# SD_w_hexconverter.net
KiCad netlist of a schematic drawn in EAGLE
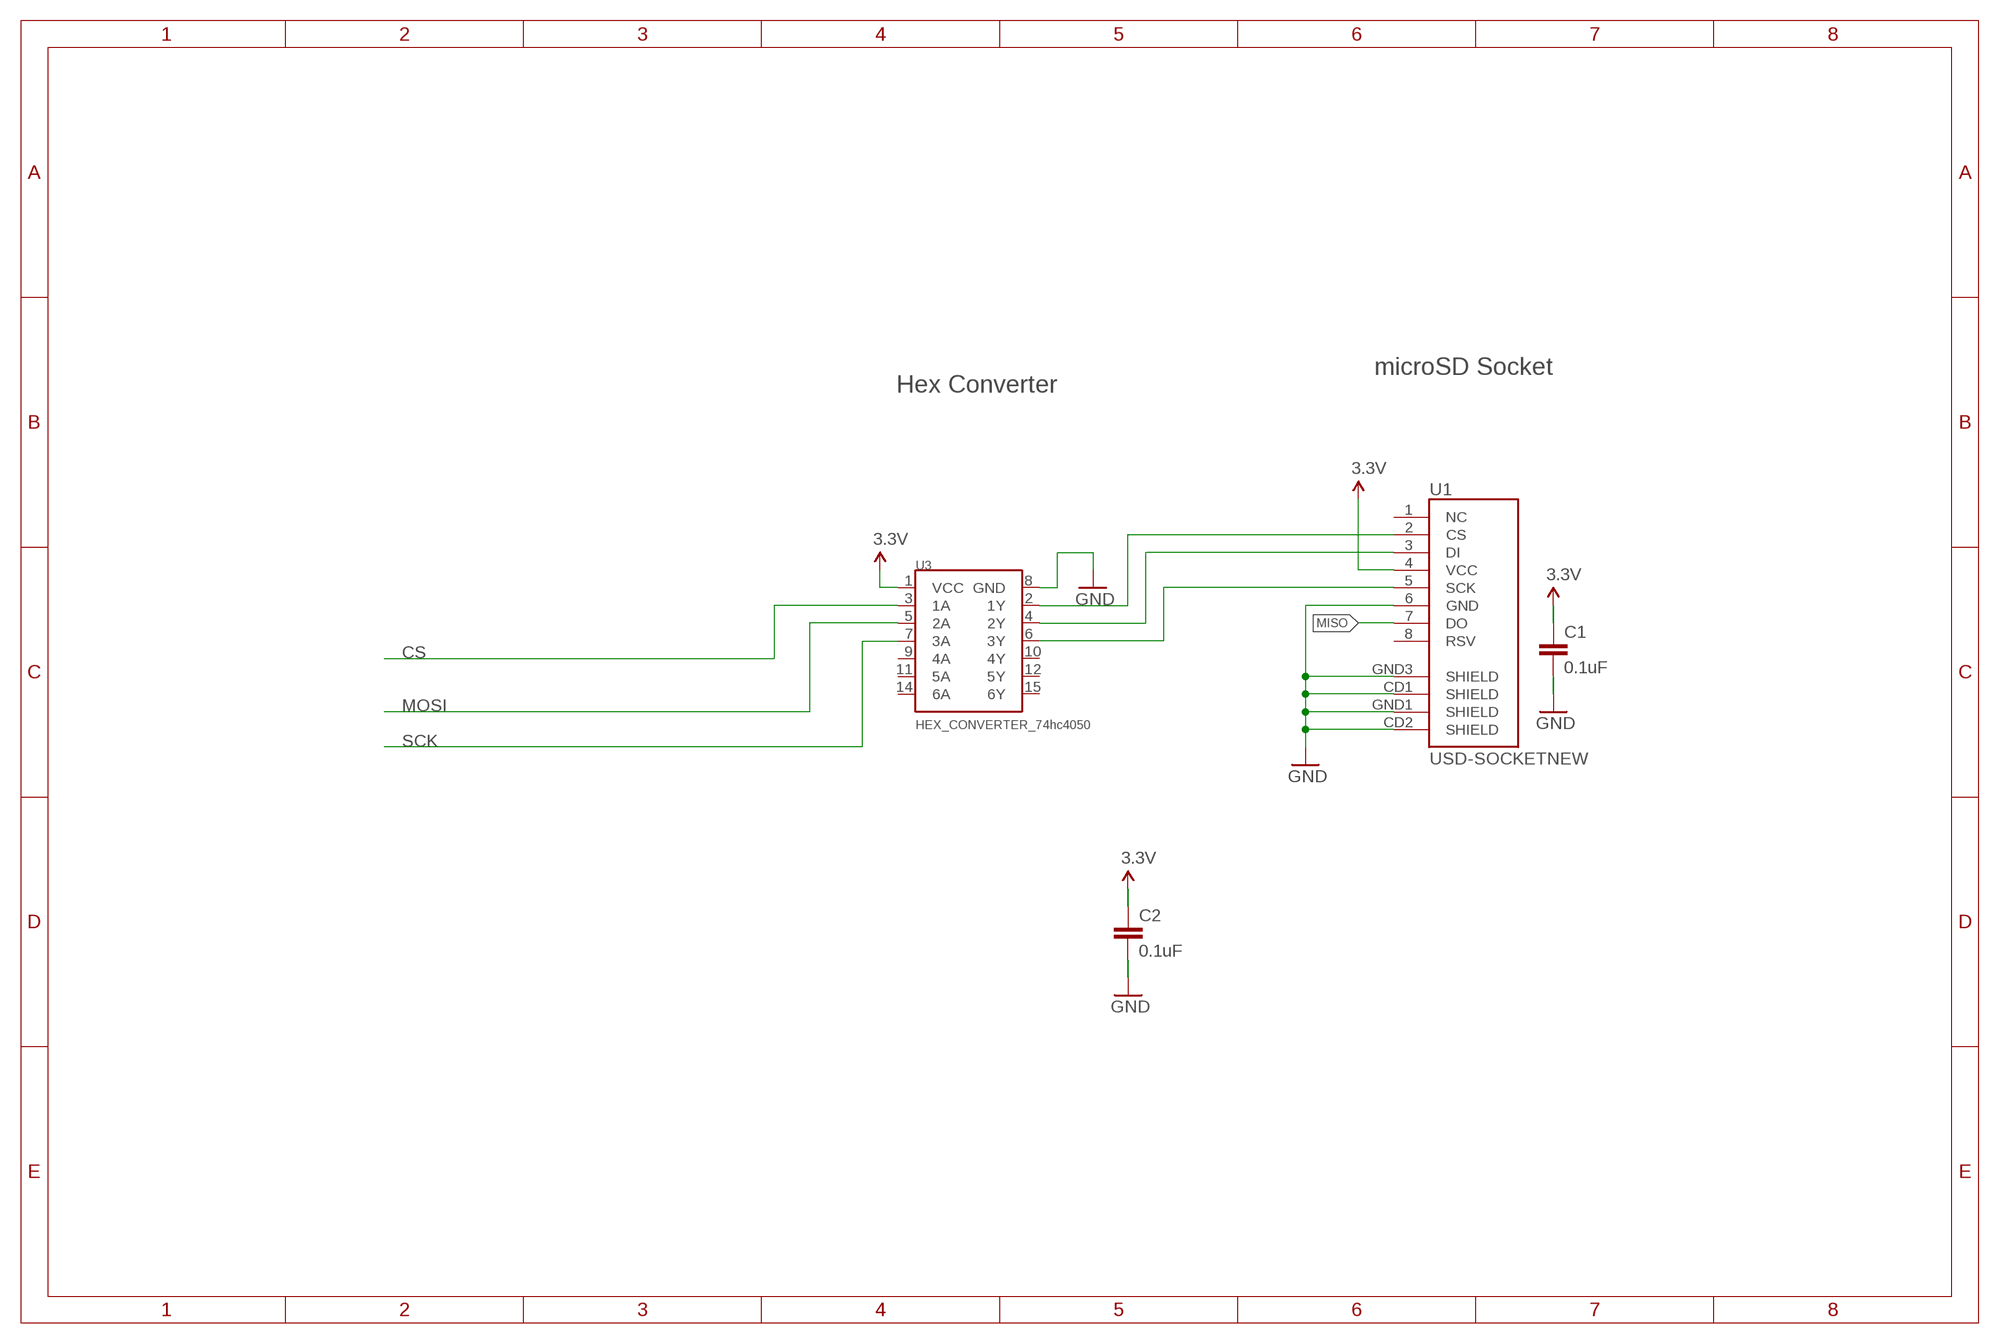
[diagram p0: schematic, sheet 1]

(export (version "E")
  (design (tool "Eeschema 10.0.6"))
  (components
    (comp (ref "C1")
      (value "0.1uF")
      (footprint "eagle-import:0603-CAP")
      (libsource (lib "eagle-import") (part "0.1UF-25V-5%(0603)"))
    )
    (comp (ref "C2")
      (value "0.1uF")
      (footprint "eagle-import:0603-CAP")
      (libsource (lib "eagle-import") (part "0.1UF-25V-5%(0603)"))
    )
    (comp (ref "U1")
      (value "USD-SOCKETNEW")
      (footprint "eagle-import:MICRO-SD-SOCKET-PP")
      (libsource (lib "eagle-import") (part "USD-SOCKETNEW"))
    )
    (comp (ref "U3")
      (value "HEX_CONVERTER_74hc4050")
      (footprint "eagle-import:SO016")
      (libsource (lib "eagle-import") (part "HEX_CONVERTER"))
    )
  )
  (nets
    (net (code "1") (name "/CS") (class "Default")
      (node (ref "U3") (pin "3") (pinfunction "1A_3") (pintype "bidirectional"))
    )
    (net (code "2") (name "/MOSI") (class "Default")
      (node (ref "U3") (pin "5") (pinfunction "2A_5") (pintype "bidirectional"))
    )
    (net (code "3") (name "/SCK") (class "Default")
      (node (ref "U3") (pin "7") (pinfunction "3A_7") (pintype "bidirectional"))
    )
    (net (code "4") (name "3.3V") (class "Default")
      (node (ref "C1") (pin "1") (pinfunction "1_1") (pintype "passive"))
      (node (ref "C2") (pin "1") (pinfunction "1_1") (pintype "passive"))
      (node (ref "U1") (pin "4") (pinfunction "VCC_4") (pintype "bidirectional"))
      (node (ref "U3") (pin "1") (pinfunction "VCC_1") (pintype "bidirectional"))
    )
    (net (code "5") (name "GND") (class "Default")
      (node (ref "C1") (pin "2") (pinfunction "2_2") (pintype "passive"))
      (node (ref "C2") (pin "2") (pinfunction "2_2") (pintype "passive"))
      (node (ref "U1") (pin "6") (pinfunction "GND_6") (pintype "bidirectional"))
      (node (ref "U1") (pin "CD1") (pinfunction "SHIELD_CD1") (pintype "bidirectional"))
      (node (ref "U1") (pin "CD2") (pinfunction "SHIELD_CD2") (pintype "bidirectional"))
      (node (ref "U1") (pin "GND1") (pinfunction "SHIELD_GND1") (pintype "bidirectional"))
      (node (ref "U1") (pin "GND3") (pinfunction "SHIELD_GND3") (pintype "bidirectional"))
      (node (ref "U3") (pin "8") (pinfunction "GND_8") (pintype "bidirectional"))
    )
    (net (code "6") (name "MISO") (class "Default")
      (node (ref "U1") (pin "7") (pinfunction "DO_7") (pintype "bidirectional"))
    )
    (net (code "7") (name "Net-(U1-CS)") (class "Default")
      (node (ref "U1") (pin "2") (pinfunction "CS_2") (pintype "bidirectional"))
      (node (ref "U3") (pin "2") (pinfunction "1Y_2") (pintype "bidirectional"))
    )
    (net (code "8") (name "Net-(U1-DI)") (class "Default")
      (node (ref "U1") (pin "3") (pinfunction "DI_3") (pintype "bidirectional"))
      (node (ref "U3") (pin "4") (pinfunction "2Y_4") (pintype "bidirectional"))
    )
    (net (code "9") (name "Net-(U1-SCK)") (class "Default")
      (node (ref "U1") (pin "5") (pinfunction "SCK_5") (pintype "bidirectional"))
      (node (ref "U3") (pin "6") (pinfunction "3Y_6") (pintype "bidirectional"))
    )
    (net (code "10") (name "unconnected-(U1-NC-Pad1)") (class "Default")
      (node (ref "U1") (pin "1") (pinfunction "NC_1") (pintype "bidirectional"))
    )
    (net (code "11") (name "unconnected-(U1-RSV-Pad8)") (class "Default")
      (node (ref "U1") (pin "8") (pinfunction "RSV_8") (pintype "bidirectional"))
    )
    (net (code "12") (name "unconnected-(U3-4A-Pad9)") (class "Default")
      (node (ref "U3") (pin "9") (pinfunction "4A_9") (pintype "bidirectional"))
    )
    (net (code "13") (name "unconnected-(U3-4Y-Pad10)") (class "Default")
      (node (ref "U3") (pin "10") (pinfunction "4Y_10") (pintype "bidirectional"))
    )
    (net (code "14") (name "unconnected-(U3-5A-Pad11)") (class "Default")
      (node (ref "U3") (pin "11") (pinfunction "5A_11") (pintype "bidirectional"))
    )
    (net (code "15") (name "unconnected-(U3-5Y-Pad12)") (class "Default")
      (node (ref "U3") (pin "12") (pinfunction "5Y_12") (pintype "bidirectional"))
    )
    (net (code "16") (name "unconnected-(U3-6A-Pad14)") (class "Default")
      (node (ref "U3") (pin "14") (pinfunction "6A_14") (pintype "bidirectional"))
    )
    (net (code "17") (name "unconnected-(U3-6Y-Pad15)") (class "Default")
      (node (ref "U3") (pin "15") (pinfunction "6Y_15") (pintype "bidirectional"))
    )
  )
)
